# TinyLispComputer.net
KiCad netlist of a schematic drawn in EAGLE
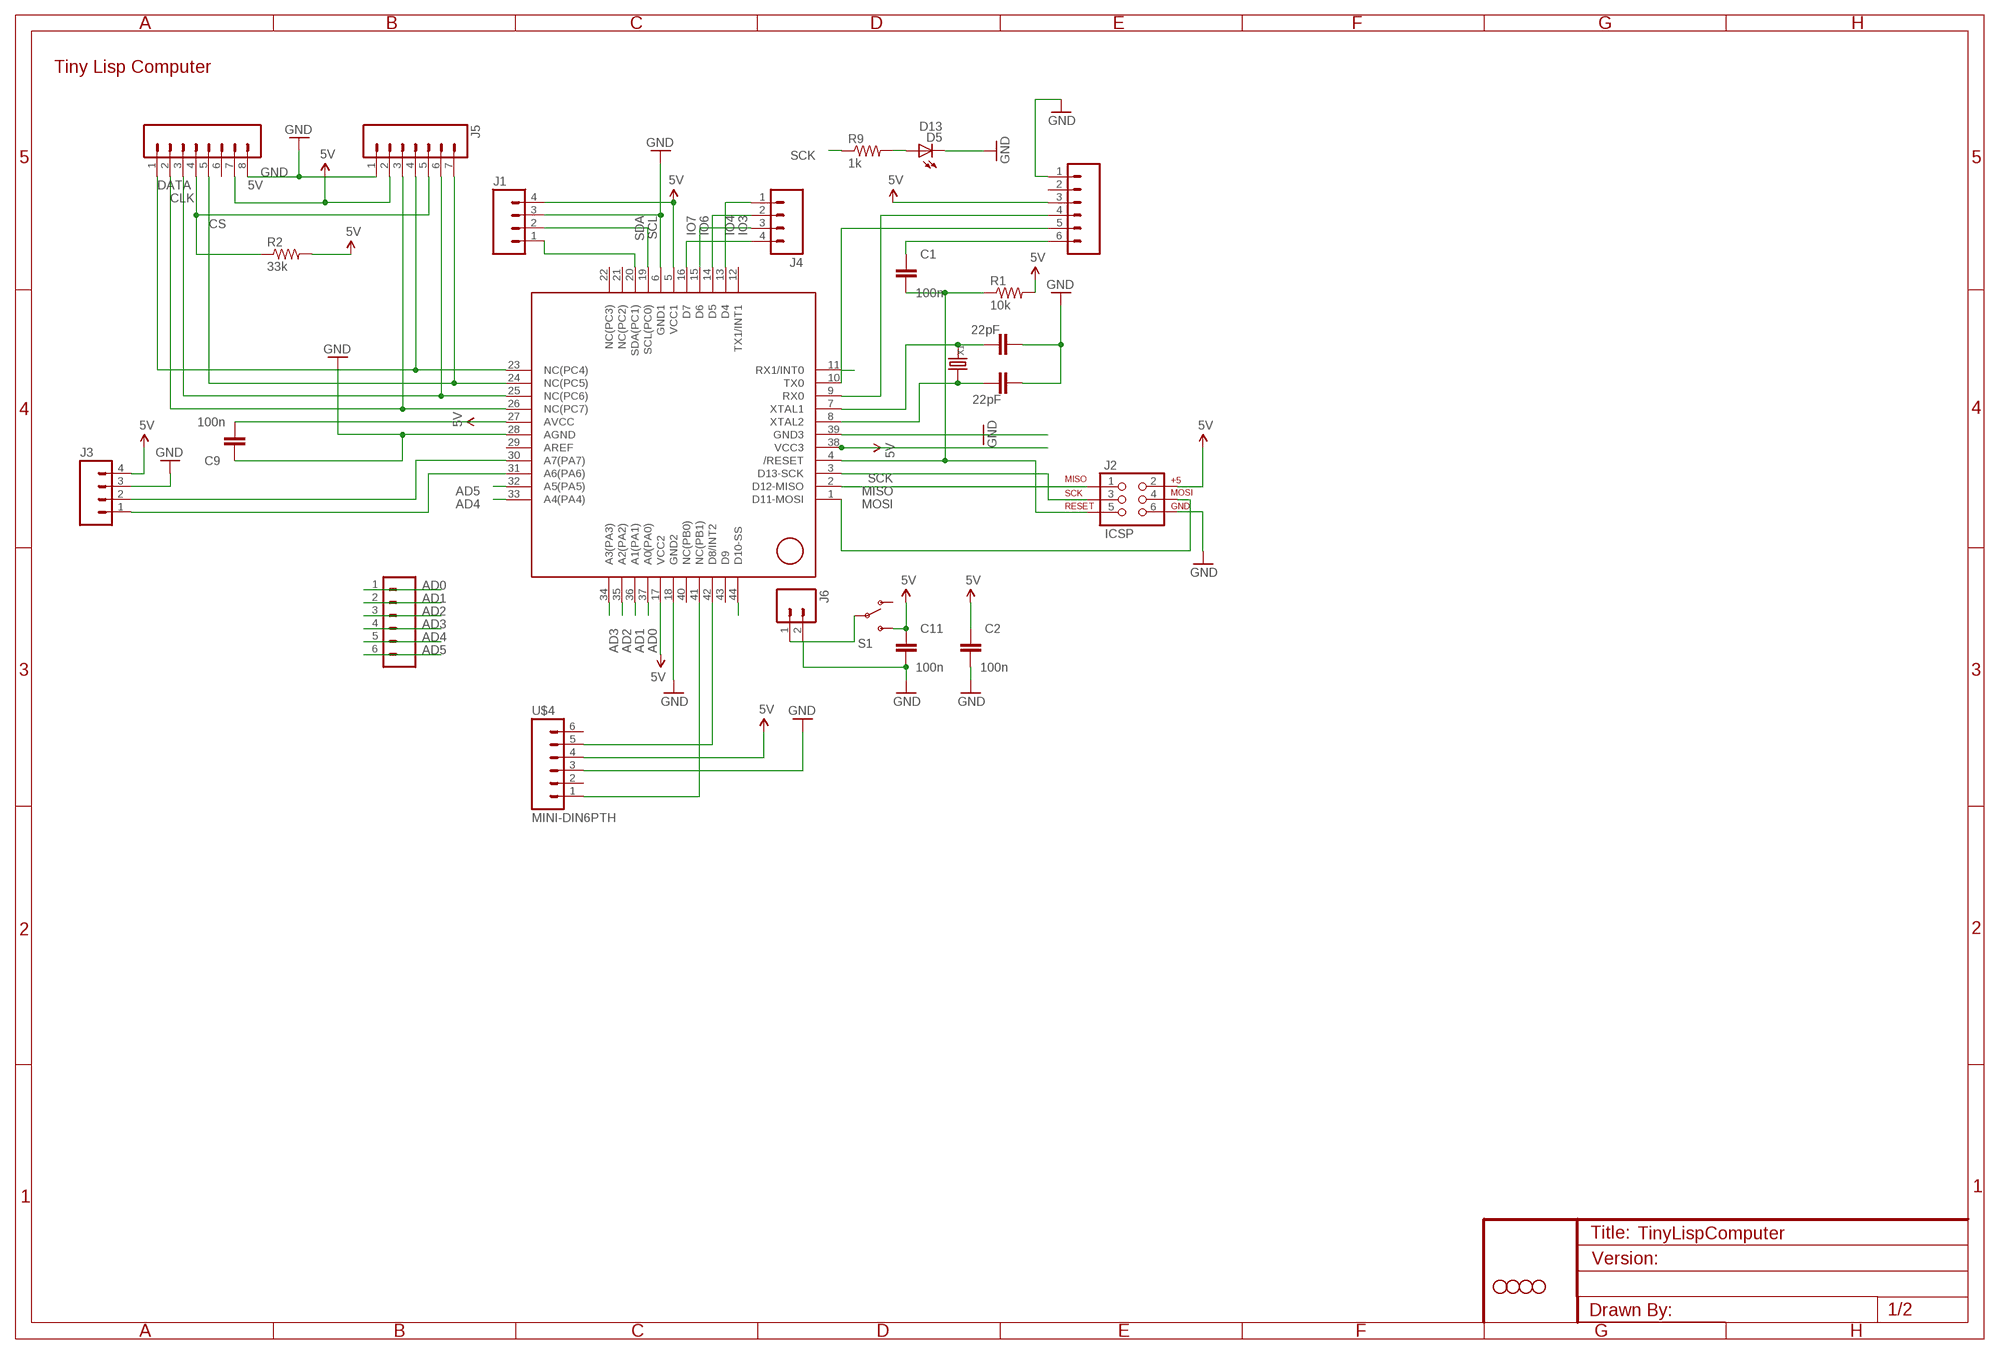
[diagram p0: schematic, sheet 1]

(export (version "E")
  (design (tool "Eeschema 10.0.6"))
  (components
    (comp (ref "C1")
      (value "100n")
      (footprint "eagle-import:0603-CAP")
      (libsource (lib "eagle-import") (part "CAP0603-CAP"))
    )
    (comp (ref "C2")
      (value "100n")
      (footprint "eagle-import:0603-CAP")
      (libsource (lib "eagle-import") (part "CAP0603-CAP"))
    )
    (comp (ref "C9")
      (value "100n")
      (footprint "eagle-import:0603-CAP")
      (libsource (lib "eagle-import") (part "CAP0603-CAP"))
    )
    (comp (ref "C11")
      (value "100n")
      (footprint "eagle-import:0603-CAP")
      (libsource (lib "eagle-import") (part "CAP0603-CAP"))
    )
    (comp (ref "C12")
      (value "22pF")
      (footprint "eagle-import:0603-CAP")
      (libsource (lib "eagle-import") (part "CAP0603-CAP"))
    )
    (comp (ref "C13")
      (value "22pF")
      (footprint "eagle-import:0603-CAP")
      (libsource (lib "eagle-import") (part "CAP0603-CAP"))
    )
    (comp (ref "D5")
      (value "D13")
      (footprint "eagle-import:CHIPLED_0805")
      (libsource (lib "eagle-import") (part "LEDCHIPLED_0805"))
    )
    (comp (ref "J1")
      (value "M04LONGPADS")
      (footprint "eagle-import:1X04_LONGPADS")
      (libsource (lib "eagle-import") (part "M04LONGPADS"))
    )
    (comp (ref "J2")
      (value "ICSP")
      (footprint "eagle-import:2X3")
      (libsource (lib "eagle-import") (part "AVR_SPI_PRG_6PTH"))
    )
    (comp (ref "J3")
      (value "M04LONGPADS")
      (footprint "eagle-import:1X04_LONGPADS")
      (libsource (lib "eagle-import") (part "M04LONGPADS"))
    )
    (comp (ref "J4")
      (value "M04LONGPADS")
      (footprint "eagle-import:1X04_LONGPADS")
      (libsource (lib "eagle-import") (part "M04LONGPADS"))
    )
    (comp (ref "J5")
      (value "M07")
      (footprint "eagle-import:1X07")
      (libsource (lib "eagle-import") (part "M07"))
    )
    (comp (ref "J6")
      (value "M021X02_NO_SILK")
      (footprint "eagle-import:1X02_NO_SILK")
      (libsource (lib "eagle-import") (part "M021X02_NO_SILK"))
    )
    (comp (ref "JP1")
      (value "M06LONGPADS")
      (footprint "eagle-import:1X06_LONGPADS")
      (libsource (lib "eagle-import") (part "M06LONGPADS"))
    )
    (comp (ref "JP3")
      (value "STAND-OFF")
      (footprint "eagle-import:STAND-OFF")
      (libsource (lib "eagle-import") (part "STAND-OFF"))
    )
    (comp (ref "JP4")
      (value "STAND-OFF")
      (footprint "eagle-import:STAND-OFF")
      (libsource (lib "eagle-import") (part "STAND-OFF"))
    )
    (comp (ref "JP5")
      (value "STAND-OFF")
      (footprint "eagle-import:STAND-OFF")
      (libsource (lib "eagle-import") (part "STAND-OFF"))
    )
    (comp (ref "JP6")
      (value "STAND-OFF")
      (footprint "eagle-import:STAND-OFF")
      (libsource (lib "eagle-import") (part "STAND-OFF"))
    )
    (comp (ref "JP11")
      (value "M06LONGPADS")
      (footprint "eagle-import:1X06_LONGPADS")
      (libsource (lib "eagle-import") (part "M06LONGPADS"))
    )
    (comp (ref "OLED")
      (value "M08")
      (footprint "eagle-import:1X08_ROUND")
      (libsource (lib "eagle-import") (part "M08"))
    )
    (comp (ref "R1")
      (value "10k")
      (footprint "eagle-import:0805")
      (libsource (lib "eagle-import") (part "0.3OHM-1/8W-1%(0805)"))
    )
    (comp (ref "R2")
      (value "33k")
      (footprint "eagle-import:0805")
      (libsource (lib "eagle-import") (part "0.3OHM-1/8W-1%(0805)"))
    )
    (comp (ref "R9")
      (value "1k")
      (footprint "eagle-import:0805")
      (libsource (lib "eagle-import") (part "0.3OHM-1/8W-1%(0805)"))
    )
    (comp (ref "S1")
      (value "SWITCH-SPDTPTH")
      (footprint "eagle-import:SWITCH-SPDT")
      (libsource (lib "eagle-import") (part "SWITCH-SPDTPTH"))
    )
    (comp (ref "U$4")
      (value "MINI-DIN6PTH")
      (footprint "eagle-import:MINI-DIN6")
      (libsource (lib "eagle-import") (part "MINI-DIN6PTH"))
    )
    (comp (ref "U3")
      (value "ATMEGA1284P")
      (footprint "eagle-import:TQFP44")
      (libsource (lib "eagle-import") (part "ATMEGA1284P"))
    )
    (comp (ref "X1")
      (value "CRYSTAL-0500290P1")
      (footprint "eagle-import:2P-SMD-5.0X3.2")
      (libsource (lib "eagle-import") (part "CRYSTAL-0500290P1"))
    )
  )
  (nets
    (net (code "1") (name "5V") (class "Default")
      (node (ref "C11") (pin "1") (pinfunction "1_1") (pintype "passive"))
      (node (ref "C2") (pin "1") (pinfunction "1_1") (pintype "passive"))
      (node (ref "C9") (pin "2") (pinfunction "2_2") (pintype "passive"))
      (node (ref "J1") (pin "4") (pinfunction "4_4") (pintype "passive"))
      (node (ref "J2") (pin "2") (pinfunction "2_2") (pintype "passive"))
      (node (ref "J3") (pin "4") (pinfunction "4_4") (pintype "passive"))
      (node (ref "J5") (pin "2") (pinfunction "2_2") (pintype "passive"))
      (node (ref "JP1") (pin "3") (pinfunction "3_3") (pintype "passive"))
      (node (ref "OLED") (pin "7") (pinfunction "7_7") (pintype "passive"))
      (node (ref "R1") (pin "2") (pinfunction "2_2") (pintype "passive"))
      (node (ref "R2") (pin "2") (pinfunction "2_2") (pintype "passive"))
      (node (ref "S1") (pin "3") (pinfunction "S_3") (pintype "passive"))
      (node (ref "U$4") (pin "4") (pinfunction "4_4") (pintype "passive"))
      (node (ref "U3") (pin "17") (pinfunction "VCC2_17") (pintype "power_in"))
      (node (ref "U3") (pin "27") (pinfunction "AVCC_27") (pintype "power_in"))
      (node (ref "U3") (pin "38") (pinfunction "VCC3_38") (pintype "power_in"))
      (node (ref "U3") (pin "5") (pinfunction "VCC1_5") (pintype "power_in"))
    )
    (net (code "2") (name "AD0") (class "Default")
      (node (ref "JP11") (pin "1") (pinfunction "1_1") (pintype "passive"))
      (node (ref "U3") (pin "37") (pinfunction "A0(PA0)_37") (pintype "bidirectional"))
    )
    (net (code "3") (name "AD1") (class "Default")
      (node (ref "JP11") (pin "2") (pinfunction "2_2") (pintype "passive"))
      (node (ref "U3") (pin "36") (pinfunction "A1(PA1)_36") (pintype "bidirectional"))
    )
    (net (code "4") (name "AD2") (class "Default")
      (node (ref "JP11") (pin "3") (pinfunction "3_3") (pintype "passive"))
      (node (ref "U3") (pin "35") (pinfunction "A2(PA2)_35") (pintype "bidirectional"))
    )
    (net (code "5") (name "AD3") (class "Default")
      (node (ref "JP11") (pin "4") (pinfunction "4_4") (pintype "passive"))
      (node (ref "U3") (pin "34") (pinfunction "A3(PA3)_34") (pintype "bidirectional"))
    )
    (net (code "6") (name "AD4") (class "Default")
      (node (ref "JP11") (pin "5") (pinfunction "5_5") (pintype "passive"))
      (node (ref "U3") (pin "33") (pinfunction "A4(PA4)_33") (pintype "bidirectional"))
    )
    (net (code "7") (name "AD5") (class "Default")
      (node (ref "JP11") (pin "6") (pinfunction "6_6") (pintype "passive"))
      (node (ref "U3") (pin "32") (pinfunction "A5(PA5)_32") (pintype "bidirectional"))
    )
    (net (code "8") (name "CLK") (class "Default")
      (node (ref "J5") (pin "6") (pinfunction "6_6") (pintype "passive"))
      (node (ref "OLED") (pin "3") (pinfunction "3_3") (pintype "passive"))
      (node (ref "U3") (pin "25") (pinfunction "NC(PC6)_25") (pintype "bidirectional"))
    )
    (net (code "9") (name "CS") (class "Default")
      (node (ref "J5") (pin "4") (pinfunction "4_4") (pintype "passive"))
      (node (ref "OLED") (pin "1") (pinfunction "1_1") (pintype "passive"))
      (node (ref "U3") (pin "23") (pinfunction "NC(PC4)_23") (pintype "bidirectional"))
    )
    (net (code "10") (name "DATA") (class "Default")
      (node (ref "J5") (pin "3") (pinfunction "3_3") (pintype "passive"))
      (node (ref "OLED") (pin "2") (pinfunction "2_2") (pintype "passive"))
      (node (ref "U3") (pin "26") (pinfunction "NC(PC7)_26") (pintype "bidirectional"))
    )
    (net (code "11") (name "GND") (class "Default")
      (node (ref "C11") (pin "2") (pinfunction "2_2") (pintype "passive"))
      (node (ref "C12") (pin "1") (pinfunction "1_1") (pintype "passive"))
      (node (ref "C13") (pin "1") (pinfunction "1_1") (pintype "passive"))
      (node (ref "C2") (pin "2") (pinfunction "2_2") (pintype "passive"))
      (node (ref "C9") (pin "1") (pinfunction "1_1") (pintype "passive"))
      (node (ref "D5") (pin "C") (pinfunction "C_C") (pintype "passive"))
      (node (ref "J1") (pin "3") (pinfunction "3_3") (pintype "passive"))
      (node (ref "J2") (pin "6") (pinfunction "6_6") (pintype "passive"))
      (node (ref "J3") (pin "3") (pinfunction "3_3") (pintype "passive"))
      (node (ref "J5") (pin "1") (pinfunction "1_1") (pintype "passive"))
      (node (ref "J6") (pin "2") (pinfunction "2_2") (pintype "passive"))
      (node (ref "JP1") (pin "1") (pinfunction "1_1") (pintype "passive"))
      (node (ref "OLED") (pin "8") (pinfunction "8_8") (pintype "passive"))
      (node (ref "U$4") (pin "3") (pinfunction "3_3") (pintype "passive"))
      (node (ref "U3") (pin "18") (pinfunction "GND2_18") (pintype "power_in"))
      (node (ref "U3") (pin "28") (pinfunction "AGND_28") (pintype "power_in"))
      (node (ref "U3") (pin "39") (pinfunction "GND3_39") (pintype "power_in"))
      (node (ref "U3") (pin "6") (pinfunction "GND1_6") (pintype "power_in"))
    )
    (net (code "12") (name "IO3") (class "Default")
      (node (ref "J4") (pin "1") (pinfunction "1_1") (pintype "passive"))
      (node (ref "U3") (pin "13") (pinfunction "D4_13") (pintype "bidirectional"))
    )
    (net (code "13") (name "IO4") (class "Default")
      (node (ref "J4") (pin "2") (pinfunction "2_2") (pintype "passive"))
      (node (ref "U3") (pin "14") (pinfunction "D5_14") (pintype "bidirectional"))
    )
    (net (code "14") (name "IO6") (class "Default")
      (node (ref "J4") (pin "3") (pinfunction "3_3") (pintype "passive"))
      (node (ref "U3") (pin "15") (pinfunction "D6_15") (pintype "bidirectional"))
    )
    (net (code "15") (name "IO7") (class "Default")
      (node (ref "J4") (pin "4") (pinfunction "4_4") (pintype "passive"))
      (node (ref "U3") (pin "16") (pinfunction "D7_16") (pintype "bidirectional"))
    )
    (net (code "16") (name "MISO") (class "Default")
      (node (ref "J2") (pin "1") (pinfunction "1_1") (pintype "passive"))
      (node (ref "U3") (pin "2") (pinfunction "D12-MISO_2") (pintype "bidirectional"))
    )
    (net (code "17") (name "MOSI") (class "Default")
      (node (ref "J2") (pin "4") (pinfunction "4_4") (pintype "passive"))
      (node (ref "U3") (pin "1") (pinfunction "D11-MOSI_1") (pintype "bidirectional"))
    )
    (net (code "18") (name "Net-(C1-Pad1)") (class "Default")
      (node (ref "C1") (pin "1") (pinfunction "1_1") (pintype "passive"))
      (node (ref "JP1") (pin "6") (pinfunction "6_6") (pintype "passive"))
    )
    (net (code "19") (name "Net-(D5-PadA)") (class "Default")
      (node (ref "D5") (pin "A") (pinfunction "A_A") (pintype "passive"))
      (node (ref "R9") (pin "2") (pinfunction "2_2") (pintype "passive"))
    )
    (net (code "20") (name "Net-(J5-Pad5)") (class "Default")
      (node (ref "J5") (pin "5") (pinfunction "5_5") (pintype "passive"))
      (node (ref "OLED") (pin "4") (pinfunction "4_4") (pintype "passive"))
      (node (ref "R2") (pin "1") (pinfunction "1_1") (pintype "passive"))
    )
    (net (code "21") (name "Net-(S1-P)") (class "Default")
      (node (ref "J6") (pin "1") (pinfunction "1_1") (pintype "passive"))
      (node (ref "S1") (pin "2") (pinfunction "P_2") (pintype "passive"))
    )
    (net (code "22") (name "Net-(U3-A6(PA6))") (class "Default")
      (node (ref "J3") (pin "1") (pinfunction "1_1") (pintype "passive"))
      (node (ref "U3") (pin "31") (pinfunction "A6(PA6)_31") (pintype "bidirectional"))
    )
    (net (code "23") (name "Net-(U3-A7(PA7))") (class "Default")
      (node (ref "J3") (pin "2") (pinfunction "2_2") (pintype "passive"))
      (node (ref "U3") (pin "30") (pinfunction "A7(PA7)_30") (pintype "bidirectional"))
    )
    (net (code "24") (name "Net-(U3-D8{slash}INT2)") (class "Default")
      (node (ref "U$4") (pin "5") (pinfunction "5_5") (pintype "passive"))
      (node (ref "U3") (pin "42") (pinfunction "D8/INT2_42") (pintype "bidirectional"))
    )
    (net (code "25") (name "Net-(U3-NC(PB1))") (class "Default")
      (node (ref "U$4") (pin "1") (pinfunction "1_1") (pintype "passive"))
      (node (ref "U3") (pin "41") (pinfunction "NC(PB1)_41") (pintype "bidirectional"))
    )
    (net (code "26") (name "Net-(U3-NC(PC5))") (class "Default")
      (node (ref "J5") (pin "7") (pinfunction "7_7") (pintype "passive"))
      (node (ref "OLED") (pin "5") (pinfunction "5_5") (pintype "passive"))
      (node (ref "U3") (pin "24") (pinfunction "NC(PC5)_24") (pintype "bidirectional"))
    )
    (net (code "27") (name "Net-(U3-RX0)") (class "Default")
      (node (ref "JP1") (pin "4") (pinfunction "4_4") (pintype "passive"))
      (node (ref "U3") (pin "9") (pinfunction "RX0_9") (pintype "bidirectional"))
    )
    (net (code "28") (name "Net-(U3-TX0)") (class "Default")
      (node (ref "JP1") (pin "5") (pinfunction "5_5") (pintype "passive"))
      (node (ref "U3") (pin "10") (pinfunction "TX0_10") (pintype "bidirectional"))
    )
    (net (code "29") (name "Net-(U3-XTAL1)") (class "Default")
      (node (ref "C12") (pin "2") (pinfunction "2_2") (pintype "passive"))
      (node (ref "U3") (pin "7") (pinfunction "XTAL1_7") (pintype "bidirectional"))
      (node (ref "X1") (pin "1") (pinfunction "1_1") (pintype "passive"))
    )
    (net (code "30") (name "Net-(U3-XTAL2)") (class "Default")
      (node (ref "C13") (pin "2") (pinfunction "2_2") (pintype "passive"))
      (node (ref "U3") (pin "8") (pinfunction "XTAL2_8") (pintype "bidirectional"))
      (node (ref "X1") (pin "2") (pinfunction "2_2") (pintype "passive"))
    )
    (net (code "31") (name "Net-(U3-{slash}RESET)") (class "Default")
      (node (ref "C1") (pin "2") (pinfunction "2_2") (pintype "passive"))
      (node (ref "J2") (pin "5") (pinfunction "5_5") (pintype "passive"))
      (node (ref "R1") (pin "1") (pinfunction "1_1") (pintype "passive"))
      (node (ref "U3") (pin "4") (pinfunction "/RESET_4") (pintype "bidirectional"))
    )
    (net (code "32") (name "SCK") (class "Default")
      (node (ref "J2") (pin "3") (pinfunction "3_3") (pintype "passive"))
      (node (ref "R9") (pin "1") (pinfunction "1_1") (pintype "passive"))
      (node (ref "U3") (pin "3") (pinfunction "D13-SCK_3") (pintype "bidirectional"))
    )
    (net (code "33") (name "SCL") (class "Default")
      (node (ref "J1") (pin "2") (pinfunction "2_2") (pintype "passive"))
      (node (ref "U3") (pin "19") (pinfunction "SCL(PC0)_19") (pintype "bidirectional"))
    )
    (net (code "34") (name "SDA") (class "Default")
      (node (ref "J1") (pin "1") (pinfunction "1_1") (pintype "passive"))
      (node (ref "U3") (pin "20") (pinfunction "SDA(PC1)_20") (pintype "bidirectional"))
    )
    (net (code "35") (name "unconnected-(JP1-Pad2)") (class "Default")
      (node (ref "JP1") (pin "2") (pinfunction "2_2") (pintype "passive"))
    )
    (net (code "36") (name "unconnected-(OLED-Pad6)") (class "Default")
      (node (ref "OLED") (pin "6") (pinfunction "6_6") (pintype "passive"))
    )
    (net (code "37") (name "unconnected-(S1-O-Pad1)") (class "Default")
      (node (ref "S1") (pin "1") (pinfunction "O_1") (pintype "passive"))
    )
    (net (code "38") (name "unconnected-(U$4-Pad2)") (class "Default")
      (node (ref "U$4") (pin "2") (pinfunction "2_2") (pintype "passive"))
    )
    (net (code "39") (name "unconnected-(U$4-Pad6)") (class "Default")
      (node (ref "U$4") (pin "6") (pinfunction "6_6") (pintype "passive"))
    )
    (net (code "40") (name "unconnected-(U3-AREF-Pad29)") (class "Default")
      (node (ref "U3") (pin "29") (pinfunction "AREF_29") (pintype "bidirectional"))
    )
    (net (code "41") (name "unconnected-(U3-D9-Pad43)") (class "Default")
      (node (ref "U3") (pin "43") (pinfunction "D9_43") (pintype "bidirectional"))
    )
    (net (code "42") (name "unconnected-(U3-D10-SS-Pad44)") (class "Default")
      (node (ref "U3") (pin "44") (pinfunction "D10-SS_44") (pintype "bidirectional"))
    )
    (net (code "43") (name "unconnected-(U3-NC(PB0)-Pad40)") (class "Default")
      (node (ref "U3") (pin "40") (pinfunction "NC(PB0)_40") (pintype "bidirectional"))
    )
    (net (code "44") (name "unconnected-(U3-NC(PC2)-Pad21)") (class "Default")
      (node (ref "U3") (pin "21") (pinfunction "NC(PC2)_21") (pintype "bidirectional"))
    )
    (net (code "45") (name "unconnected-(U3-NC(PC3)-Pad22)") (class "Default")
      (node (ref "U3") (pin "22") (pinfunction "NC(PC3)_22") (pintype "bidirectional"))
    )
    (net (code "46") (name "unconnected-(U3-RX1{slash}INT0-Pad11)") (class "Default")
      (node (ref "U3") (pin "11") (pinfunction "RX1/INT0_11") (pintype "bidirectional"))
    )
    (net (code "47") (name "unconnected-(U3-TX1{slash}INT1-Pad12)") (class "Default")
      (node (ref "U3") (pin "12") (pinfunction "TX1/INT1_12") (pintype "bidirectional"))
    )
  )
)
